# LionIRVT-TM4C_Power.net
KiCad netlist of a schematic drawn in Altium Designer
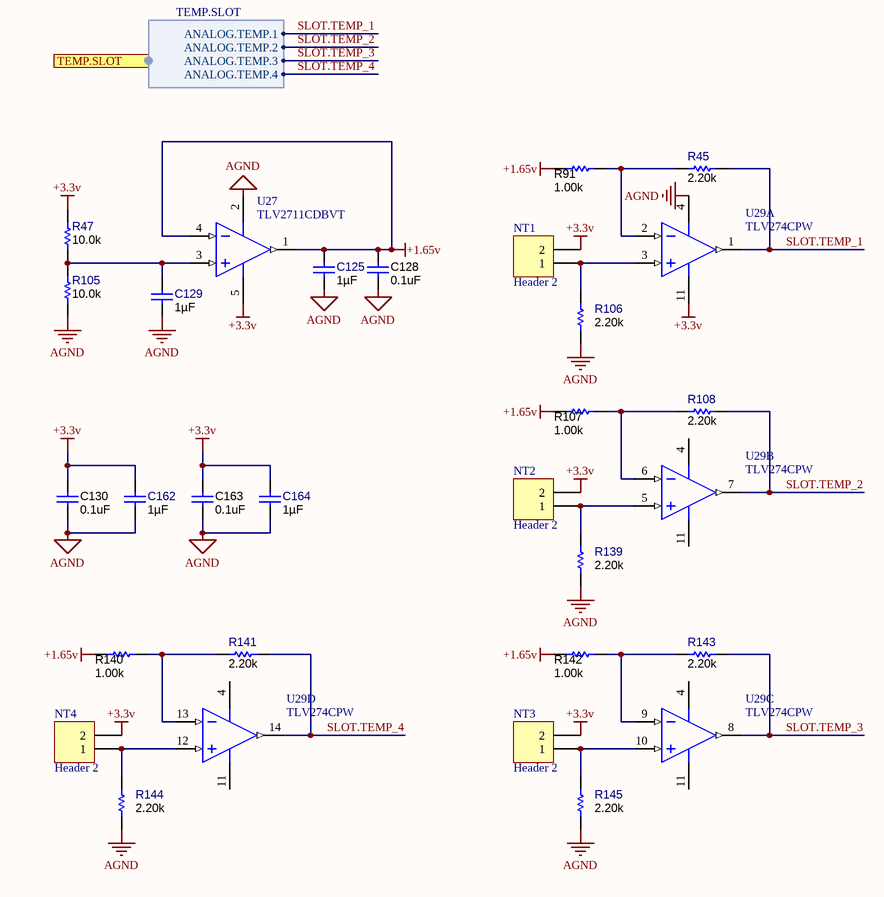
[diagram p0: LionIRVT-TM4C_Power.SchDoc]

(export (version "E")
  (design (tool "Eeschema 10.0.6"))
  (components
    (comp (ref "C125")
      (value "C0603C105K3RACTU")
      (footprint "0603C")
      (description "CAP, CERM, 1 µF, 25 V, +/- 10%, X7R, 0603")
      (fields
        (field (name "VALUEDISPLAYED") "1µF")
        (field (name "MANUFACTURER") "Kemet")
        (field (name "PUBLISHER") "Texas Instruments")
      )
      (libsource (lib "Capacitor_Ceramic") (part "C0603C105K3RACTU"))
    )
    (comp (ref "C128")
      (value "Capacitor")
      (footprint "0603C")
      (description "CAP, CERM, 0.1 uF, 25 V, +/- 5%, X7R, 0603")
      (fields
        (field (name "PARTNUMBER") "06033C104JAT2A")
        (field (name "VALUEDISPLAYED") "0.1uF")
        (field (name "MANUFACTURER") "AVX")
        (field (name "PUBLISHER") "Texas Instruments")
      )
      (libsource (lib "SV601272A") (part "CMP-0006752-5"))
    )
    (comp (ref "C129")
      (value "C0603C105K3RACTU")
      (footprint "0603C")
      (description "CAP, CERM, 1 µF, 25 V, +/- 10%, X7R, 0603")
      (fields
        (field (name "VALUEDISPLAYED") "1µF")
        (field (name "MANUFACTURER") "Kemet")
        (field (name "PUBLISHER") "Texas Instruments")
      )
      (libsource (lib "Capacitor_Ceramic") (part "C0603C105K3RACTU"))
    )
    (comp (ref "C130")
      (value "Capacitor")
      (footprint "0603C")
      (description "CAP, CERM, 0.1 uF, 25 V, +/- 5%, X7R, 0603")
      (fields
        (field (name "PARTNUMBER") "06033C104JAT2A")
        (field (name "VALUEDISPLAYED") "0.1uF")
        (field (name "MANUFACTURER") "AVX")
        (field (name "PUBLISHER") "Texas Instruments")
      )
      (libsource (lib "SV601272A") (part "CMP-0006752-5"))
    )
    (comp (ref "C162")
      (value "C0603C105K3RACTU")
      (footprint "0603C")
      (description "CAP, CERM, 1 µF, 25 V, +/- 10%, X7R, 0603")
      (fields
        (field (name "VALUEDISPLAYED") "1µF")
        (field (name "MANUFACTURER") "Kemet")
        (field (name "PUBLISHER") "Texas Instruments")
      )
      (libsource (lib "Capacitor_Ceramic") (part "C0603C105K3RACTU"))
    )
    (comp (ref "C163")
      (value "Capacitor")
      (footprint "0603C")
      (description "CAP, CERM, 0.1 uF, 25 V, +/- 5%, X7R, 0603")
      (fields
        (field (name "PARTNUMBER") "06033C104JAT2A")
        (field (name "VALUEDISPLAYED") "0.1uF")
        (field (name "MANUFACTURER") "AVX")
        (field (name "PUBLISHER") "Texas Instruments")
      )
      (libsource (lib "SV601272A") (part "CMP-0006752-5"))
    )
    (comp (ref "C164")
      (value "C0603C105K3RACTU")
      (footprint "0603C")
      (description "CAP, CERM, 1 µF, 25 V, +/- 10%, X7R, 0603")
      (fields
        (field (name "VALUEDISPLAYED") "1µF")
        (field (name "MANUFACTURER") "Kemet")
        (field (name "PUBLISHER") "Texas Instruments")
      )
      (libsource (lib "Capacitor_Ceramic") (part "C0603C105K3RACTU"))
    )
    (comp (ref "NT1")
      (value "Header 2")
      (footprint "HDR1X2")
      (description "Header, 2-Pin")
      (fields (field (name "PUBLISHER") "Altium Limited"))
      (libsource (lib "Miscellaneous Connectors") (part "Header 2"))
    )
    (comp (ref "NT2")
      (value "Header 2")
      (footprint "HDR1X2")
      (description "Header, 2-Pin")
      (fields (field (name "PUBLISHER") "Altium Limited"))
      (libsource (lib "Miscellaneous Connectors") (part "Header 2"))
    )
    (comp (ref "NT3")
      (value "Header 2")
      (footprint "HDR1X2")
      (description "Header, 2-Pin")
      (fields (field (name "PUBLISHER") "Altium Limited"))
      (libsource (lib "Miscellaneous Connectors") (part "Header 2"))
    )
    (comp (ref "NT4")
      (value "Header 2")
      (footprint "HDR1X2")
      (description "Header, 2-Pin")
      (fields (field (name "PUBLISHER") "Altium Limited"))
      (libsource (lib "Miscellaneous Connectors") (part "Header 2"))
    )
    (comp (ref "R45")
      (value "RC0603FR-072K2L")
      (footprint "0603R")
      (description "RES, 2.20 k, 1%, 0.1 W, 0603")
      (fields
        (field (name "VALUEDISPLAYED") "2.20k")
        (field (name "MANUFACTURER") "Yageo America")
        (field (name "PUBLISHER") "Texas Instruments")
      )
      (libsource (lib "Resistor_0603") (part "RC0603FR-072K2L"))
    )
    (comp (ref "R47")
      (value "RC0603FR-0710KL")
      (footprint "0603R")
      (description "RES, 10.0 k, 1%, 0.1 W, 0603")
      (fields
        (field (name "VALUEDISPLAYED") "10.0k")
        (field (name "MANUFACTURER") "Yageo America")
        (field (name "PUBLISHER") "Texas Instruments")
      )
      (libsource (lib "Resistor_0603") (part "RC0603FR-0710KL"))
    )
    (comp (ref "R91")
      (value "Resistor")
      (footprint "0603R")
      (description "RES, 1.00 k, 1%, 0.1 W, AEC-Q200 Grade 0, 0603")
      (fields
        (field (name "PARTNUMBER") "CRCW06031K00FKEA")
        (field (name "MANUFACTURER") "Vishay-Dale")
        (field (name "VALUEDISPLAYED") "1.00k")
      )
      (libsource (lib "PMP40182") (part "CMP-0022109-5"))
    )
    (comp (ref "R105")
      (value "RC0603FR-0710KL")
      (footprint "0603R")
      (description "RES, 10.0 k, 1%, 0.1 W, 0603")
      (fields
        (field (name "VALUEDISPLAYED") "10.0k")
        (field (name "MANUFACTURER") "Yageo America")
        (field (name "PUBLISHER") "Texas Instruments")
      )
      (libsource (lib "Resistor_0603") (part "RC0603FR-0710KL"))
    )
    (comp (ref "R106")
      (value "RC0603FR-072K2L")
      (footprint "0603R")
      (description "RES, 2.20 k, 1%, 0.1 W, 0603")
      (fields
        (field (name "VALUEDISPLAYED") "2.20k")
        (field (name "MANUFACTURER") "Yageo America")
        (field (name "PUBLISHER") "Texas Instruments")
      )
      (libsource (lib "Resistor_0603") (part "RC0603FR-072K2L"))
    )
    (comp (ref "R107")
      (value "Resistor")
      (footprint "0603R")
      (description "RES, 1.00 k, 1%, 0.1 W, AEC-Q200 Grade 0, 0603")
      (fields
        (field (name "PARTNUMBER") "CRCW06031K00FKEA")
        (field (name "MANUFACTURER") "Vishay-Dale")
        (field (name "VALUEDISPLAYED") "1.00k")
      )
      (libsource (lib "PMP40182") (part "CMP-0022109-5"))
    )
    (comp (ref "R108")
      (value "RC0603FR-072K2L")
      (footprint "0603R")
      (description "RES, 2.20 k, 1%, 0.1 W, 0603")
      (fields
        (field (name "VALUEDISPLAYED") "2.20k")
        (field (name "MANUFACTURER") "Yageo America")
        (field (name "PUBLISHER") "Texas Instruments")
      )
      (libsource (lib "Resistor_0603") (part "RC0603FR-072K2L"))
    )
    (comp (ref "R139")
      (value "RC0603FR-072K2L")
      (footprint "0603R")
      (description "RES, 2.20 k, 1%, 0.1 W, 0603")
      (fields
        (field (name "VALUEDISPLAYED") "2.20k")
        (field (name "MANUFACTURER") "Yageo America")
        (field (name "PUBLISHER") "Texas Instruments")
      )
      (libsource (lib "Resistor_0603") (part "RC0603FR-072K2L"))
    )
    (comp (ref "R140")
      (value "Resistor")
      (footprint "0603R")
      (description "RES, 1.00 k, 1%, 0.1 W, AEC-Q200 Grade 0, 0603")
      (fields
        (field (name "PARTNUMBER") "CRCW06031K00FKEA")
        (field (name "MANUFACTURER") "Vishay-Dale")
        (field (name "VALUEDISPLAYED") "1.00k")
      )
      (libsource (lib "PMP40182") (part "CMP-0022109-5"))
    )
    (comp (ref "R141")
      (value "RC0603FR-072K2L")
      (footprint "0603R")
      (description "RES, 2.20 k, 1%, 0.1 W, 0603")
      (fields
        (field (name "VALUEDISPLAYED") "2.20k")
        (field (name "MANUFACTURER") "Yageo America")
        (field (name "PUBLISHER") "Texas Instruments")
      )
      (libsource (lib "Resistor_0603") (part "RC0603FR-072K2L"))
    )
    (comp (ref "R142")
      (value "Resistor")
      (footprint "0603R")
      (description "RES, 1.00 k, 1%, 0.1 W, AEC-Q200 Grade 0, 0603")
      (fields
        (field (name "PARTNUMBER") "CRCW06031K00FKEA")
        (field (name "MANUFACTURER") "Vishay-Dale")
        (field (name "VALUEDISPLAYED") "1.00k")
      )
      (libsource (lib "PMP40182") (part "CMP-0022109-5"))
    )
    (comp (ref "R143")
      (value "RC0603FR-072K2L")
      (footprint "0603R")
      (description "RES, 2.20 k, 1%, 0.1 W, 0603")
      (fields
        (field (name "VALUEDISPLAYED") "2.20k")
        (field (name "MANUFACTURER") "Yageo America")
        (field (name "PUBLISHER") "Texas Instruments")
      )
      (libsource (lib "Resistor_0603") (part "RC0603FR-072K2L"))
    )
    (comp (ref "R144")
      (value "RC0603FR-072K2L")
      (footprint "0603R")
      (description "RES, 2.20 k, 1%, 0.1 W, 0603")
      (fields
        (field (name "VALUEDISPLAYED") "2.20k")
        (field (name "MANUFACTURER") "Yageo America")
        (field (name "PUBLISHER") "Texas Instruments")
      )
      (libsource (lib "Resistor_0603") (part "RC0603FR-072K2L"))
    )
    (comp (ref "R145")
      (value "RC0603FR-072K2L")
      (footprint "0603R")
      (description "RES, 2.20 k, 1%, 0.1 W, 0603")
      (fields
        (field (name "VALUEDISPLAYED") "2.20k")
        (field (name "MANUFACTURER") "Yageo America")
        (field (name "PUBLISHER") "Texas Instruments")
      )
      (libsource (lib "Resistor_0603") (part "RC0603FR-072K2L"))
    )
    (comp (ref "U27")
      (value "TLV2711CDBVT")
      (footprint "DBV0005A_M")
      (fields (field (name "MANUFACTURER") "Texas Instruments"))
      (libsource (lib "Altium Content Vault") (part "TI-TLV27X1DBV5"))
    )
    (comp (ref "U29")
      (value "TLV274CPW")
      (footprint "PW0014A_M")
      (fields (field (name "MANUFACTURER") "Texas Instruments"))
      (libsource (lib "Altium Content Vault") (part "TI-TLC_TLV_TLC1079-14"))
    )
  )
  (nets
    (net (code "2") (name "+1.65v") (class "Default")
      (node (ref "C125") (pin "2") (pinfunction "2_2") (pintype "passive"))
      (node (ref "C128") (pin "1") (pinfunction "1_1") (pintype "passive"))
      (node (ref "R107") (pin "2") (pinfunction "2_2") (pintype "passive"))
      (node (ref "R140") (pin "2") (pinfunction "2_2") (pintype "passive"))
      (node (ref "R142") (pin "2") (pinfunction "2_2") (pintype "passive"))
      (node (ref "R91") (pin "2") (pinfunction "2_2") (pintype "passive"))
      (node (ref "U27") (pin "1") (pinfunction "OUT_1") (pintype "output"))
      (node (ref "U27") (pin "4") (pinfunction "IN-_4") (pintype "input"))
    )
    (net (code "3") (name "+3.3v") (class "Default")
      (node (ref "C130") (pin "1") (pinfunction "1_1") (pintype "passive"))
      (node (ref "C162") (pin "2") (pinfunction "2_2") (pintype "passive"))
      (node (ref "C163") (pin "1") (pinfunction "1_1") (pintype "passive"))
      (node (ref "C164") (pin "2") (pinfunction "2_2") (pintype "passive"))
      (node (ref "NT1") (pin "2") (pinfunction "2_2") (pintype "passive"))
      (node (ref "NT2") (pin "2") (pinfunction "2_2") (pintype "passive"))
      (node (ref "NT3") (pin "2") (pinfunction "2_2") (pintype "passive"))
      (node (ref "NT4") (pin "2") (pinfunction "2_2") (pintype "passive"))
      (node (ref "R47") (pin "1") (pinfunction "1_1") (pintype "passive"))
      (node (ref "U27") (pin "5") (pinfunction "VDD-/GND_5") (pintype "power_in"))
      (node (ref "U29") (pin "11") (pinfunction "GND_11") (pintype "power_in"))
    )
    (net (code "4") (name "/SLOT.TEMP_1") (class "Default")
      (node (ref "R45") (pin "1") (pinfunction "1_1") (pintype "passive"))
      (node (ref "U29") (pin "1") (pinfunction "OUT1_1") (pintype "output"))
    )
    (net (code "5") (name "/SLOT.TEMP_2") (class "Default")
      (node (ref "R108") (pin "1") (pinfunction "1_1") (pintype "passive"))
      (node (ref "U29") (pin "7") (pinfunction "OUT2_7") (pintype "output"))
    )
    (net (code "6") (name "/SLOT.TEMP_3") (class "Default")
      (node (ref "R143") (pin "1") (pinfunction "1_1") (pintype "passive"))
      (node (ref "U29") (pin "8") (pinfunction "OUT3_8") (pintype "output"))
    )
    (net (code "7") (name "/SLOT.TEMP_4") (class "Default")
      (node (ref "R141") (pin "1") (pinfunction "1_1") (pintype "passive"))
      (node (ref "U29") (pin "14") (pinfunction "OUT4_14") (pintype "output"))
    )
    (net (code "9") (name "AGND") (class "Default")
      (node (ref "C125") (pin "1") (pinfunction "1_1") (pintype "passive"))
      (node (ref "C128") (pin "2") (pinfunction "2_2") (pintype "passive"))
      (node (ref "C129") (pin "1") (pinfunction "1_1") (pintype "passive"))
      (node (ref "C130") (pin "2") (pinfunction "2_2") (pintype "passive"))
      (node (ref "C162") (pin "1") (pinfunction "1_1") (pintype "passive"))
      (node (ref "C163") (pin "2") (pinfunction "2_2") (pintype "passive"))
      (node (ref "C164") (pin "1") (pinfunction "1_1") (pintype "passive"))
      (node (ref "R105") (pin "2") (pinfunction "2_2") (pintype "passive"))
      (node (ref "R106") (pin "1") (pinfunction "1_1") (pintype "passive"))
      (node (ref "R139") (pin "1") (pinfunction "1_1") (pintype "passive"))
      (node (ref "R144") (pin "1") (pinfunction "1_1") (pintype "passive"))
      (node (ref "R145") (pin "1") (pinfunction "1_1") (pintype "passive"))
      (node (ref "U27") (pin "2") (pinfunction "VDD+_2") (pintype "power_in"))
      (node (ref "U29") (pin "4") (pinfunction "VDD_4") (pintype "power_in"))
    )
    (net (code "10") (name "Net-(U27-IN+)") (class "Default")
      (node (ref "C129") (pin "2") (pinfunction "2_2") (pintype "passive"))
      (node (ref "R105") (pin "1") (pinfunction "1_1") (pintype "passive"))
      (node (ref "R47") (pin "2") (pinfunction "2_2") (pintype "passive"))
      (node (ref "U27") (pin "3") (pinfunction "IN+_3") (pintype "input"))
    )
    (net (code "11") (name "Net-(U29A-IN1+)") (class "Default")
      (node (ref "NT1") (pin "1") (pinfunction "1_1") (pintype "passive"))
      (node (ref "R106") (pin "2") (pinfunction "2_2") (pintype "passive"))
      (node (ref "U29") (pin "3") (pinfunction "IN1+_3") (pintype "input"))
    )
    (net (code "12") (name "Net-(U29A-IN1-)") (class "Default")
      (node (ref "R45") (pin "2") (pinfunction "2_2") (pintype "passive"))
      (node (ref "R91") (pin "1") (pinfunction "1_1") (pintype "passive"))
      (node (ref "U29") (pin "2") (pinfunction "IN1-_2") (pintype "input"))
    )
    (net (code "13") (name "Net-(U29B-IN2+)") (class "Default")
      (node (ref "NT2") (pin "1") (pinfunction "1_1") (pintype "passive"))
      (node (ref "R139") (pin "2") (pinfunction "2_2") (pintype "passive"))
      (node (ref "U29") (pin "5") (pinfunction "IN2+_5") (pintype "input"))
    )
    (net (code "14") (name "Net-(U29B-IN2-)") (class "Default")
      (node (ref "R107") (pin "1") (pinfunction "1_1") (pintype "passive"))
      (node (ref "R108") (pin "2") (pinfunction "2_2") (pintype "passive"))
      (node (ref "U29") (pin "6") (pinfunction "IN2-_6") (pintype "input"))
    )
    (net (code "15") (name "Net-(U29C-IN3+)") (class "Default")
      (node (ref "NT3") (pin "1") (pinfunction "1_1") (pintype "passive"))
      (node (ref "R145") (pin "2") (pinfunction "2_2") (pintype "passive"))
      (node (ref "U29") (pin "10") (pinfunction "IN3+_10") (pintype "input"))
    )
    (net (code "16") (name "Net-(U29C-IN3-)") (class "Default")
      (node (ref "R142") (pin "1") (pinfunction "1_1") (pintype "passive"))
      (node (ref "R143") (pin "2") (pinfunction "2_2") (pintype "passive"))
      (node (ref "U29") (pin "9") (pinfunction "IN3-_9") (pintype "input"))
    )
    (net (code "17") (name "Net-(U29D-IN4+)") (class "Default")
      (node (ref "NT4") (pin "1") (pinfunction "1_1") (pintype "passive"))
      (node (ref "R144") (pin "2") (pinfunction "2_2") (pintype "passive"))
      (node (ref "U29") (pin "12") (pinfunction "IN4+_12") (pintype "input"))
    )
    (net (code "18") (name "Net-(U29D-IN4-)") (class "Default")
      (node (ref "R140") (pin "1") (pinfunction "1_1") (pintype "passive"))
      (node (ref "R141") (pin "2") (pinfunction "2_2") (pintype "passive"))
      (node (ref "U29") (pin "13") (pinfunction "IN4-_13") (pintype "input"))
    )
    (net (code "19") (name "unconnected-(U29B-GND-Pad11)") (class "Default")
      (node (ref "U29") (pin "11") (pinfunction "GND_11") (pintype "power_in"))
    )
    (net (code "20") (name "unconnected-(U29B-VDD-Pad4)") (class "Default")
      (node (ref "U29") (pin "4") (pinfunction "VDD_4") (pintype "power_in"))
    )
    (net (code "21") (name "unconnected-(U29C-GND-Pad11)") (class "Default")
      (node (ref "U29") (pin "11") (pinfunction "GND_11") (pintype "power_in"))
    )
    (net (code "22") (name "unconnected-(U29C-VDD-Pad4)") (class "Default")
      (node (ref "U29") (pin "4") (pinfunction "VDD_4") (pintype "power_in"))
    )
    (net (code "23") (name "unconnected-(U29D-GND-Pad11)") (class "Default")
      (node (ref "U29") (pin "11") (pinfunction "GND_11") (pintype "power_in"))
    )
    (net (code "24") (name "unconnected-(U29D-VDD-Pad4)") (class "Default")
      (node (ref "U29") (pin "4") (pinfunction "VDD_4") (pintype "power_in"))
    )
  )
)
